# IEPE_POWER.net
KiCad netlist of a schematic drawn in Altium Designer
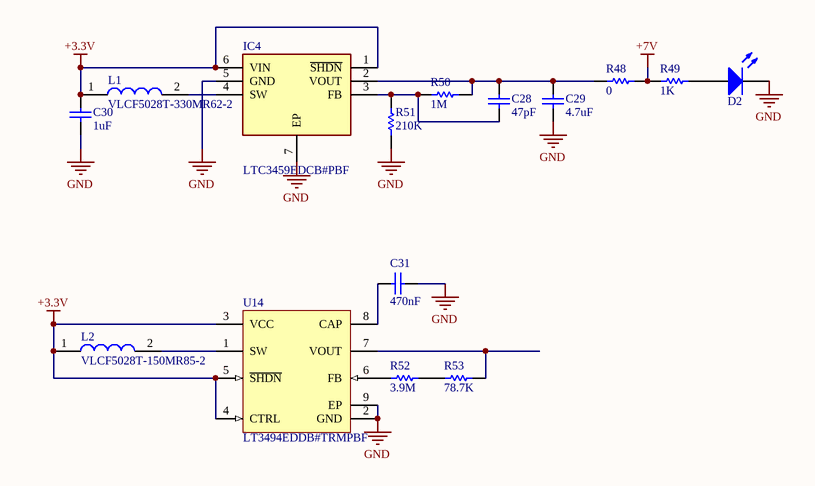
[diagram p0: IEPE_POWER.SchDoc]

(export (version "E")
  (design (tool "Eeschema 10.0.6"))
  (components
    (comp (ref "C28")
      (value "47pF")
      (footprint "c603")
      (description "Capacitor")
      (fields (field (name "DESIGNER") "Parsa Malekpour"))
      (libsource (lib "ParsaLibrary") (part "Cap"))
    )
    (comp (ref "C29")
      (value "4.7uF")
      (footprint "C805")
      (description "Capacitor")
      (fields (field (name "DESIGNER") "Parsa Malekpour"))
      (libsource (lib "ParsaLibrary") (part "Cap"))
    )
    (comp (ref "C30")
      (value "1uF")
      (footprint "c603")
      (description "Capacitor")
      (fields (field (name "DESIGNER") "Parsa Malekpour"))
      (libsource (lib "ParsaLibrary") (part "Cap"))
    )
    (comp (ref "C31")
      (value "470nF")
      (footprint "c603")
      (description "Capacitor")
      (fields (field (name "DESIGNER") "Parsa Malekpour"))
      (libsource (lib "ParsaLibrary") (part "Cap"))
    )
    (comp (ref "D2") (value "LED") (footprint "led-0603") (libsource (lib "ParsaLibrary") (part "LED")))
    (comp (ref "IC4")
      (value "LTC3459EDCB#PBF")
      (footprint "SamacSys:SON50P300X200X80-7N-D")
      (description "Integrated Circuit")
      (fields (field (name "MOUSER PART NUMBER") "584-LTC3459EDCB#PBF"))
      (libsource (lib "*") (part "LTC3459EDCB#PBF"))
    )
    (comp (ref "L1")
      (value "VLCF5028T-330MR62-2")
      (footprint "SamacSys:VLCF5028")
      (description "Inductor")
      (fields (field (name "MOUSER PART NUMBER") "810-VLCF528T330MR622"))
      (libsource (lib "*") (part "VLCF5028T-330MR62-2"))
    )
    (comp (ref "L2")
      (value "VLCF5028T-150MR85-2")
      (footprint "SamacSys:VLCF5028")
      (description "Inductor")
      (fields (field (name "MOUSER PART NUMBER") "810-VLCF528T150MR852"))
      (libsource (lib "*") (part "VLCF5028T-150MR85-2"))
    )
    (comp (ref "R48")
      (value "0")
      (footprint "R0603")
      (description "Resistor")
      (fields (field (name "DESIGNER") "Parsa Malekpour"))
      (libsource (lib "ParsaLibrary") (part "Resistor"))
    )
    (comp (ref "R49")
      (value "1K")
      (footprint "R0603")
      (description "Resistor")
      (fields (field (name "DESIGNER") "Parsa Malekpour"))
      (libsource (lib "ParsaLibrary") (part "Resistor"))
    )
    (comp (ref "R50")
      (value "1M")
      (footprint "R0603")
      (description "Resistor")
      (fields (field (name "DESIGNER") "Parsa Malekpour"))
      (libsource (lib "ParsaLibrary") (part "Resistor"))
    )
    (comp (ref "R51")
      (value "210K")
      (footprint "R0603")
      (description "Resistor")
      (fields (field (name "DESIGNER") "Parsa Malekpour"))
      (libsource (lib "ParsaLibrary") (part "Resistor"))
    )
    (comp (ref "R52")
      (value "3.9M")
      (footprint "R0603")
      (description "Resistor")
      (fields (field (name "DESIGNER") "Parsa Malekpour"))
      (libsource (lib "ParsaLibrary") (part "Resistor"))
    )
    (comp (ref "R53")
      (value "78.7K")
      (footprint "R0603")
      (description "Resistor")
      (fields (field (name "DESIGNER") "Parsa Malekpour"))
      (libsource (lib "ParsaLibrary") (part "Resistor"))
    )
    (comp (ref "U14")
      (value "LT3494EDDB#TRMPBF")
      (footprint "LT-DDB-8_V")
      (fields (field (name "MANUFACTURER") "Linear Technology"))
      (libsource (lib "Altium Content Vault") (part "LT-LT3494X-DDB-8_A"))
    )
  )
  (nets
    (net (code "1") (name "+3.3V") (class "Default")
      (node (ref "C30") (pin "2") (pinfunction "2_2") (pintype "passive"))
      (node (ref "IC4") (pin "1") (pinfunction "~{SHDN}_1") (pintype "passive"))
      (node (ref "IC4") (pin "6") (pinfunction "VIN_6") (pintype "passive"))
      (node (ref "L1") (pin "1") (pinfunction "1_1") (pintype "passive"))
      (node (ref "L2") (pin "1") (pinfunction "1_1") (pintype "passive"))
      (node (ref "U14") (pin "3") (pinfunction "VCC_3") (pintype "power_in"))
      (node (ref "U14") (pin "4") (pinfunction "CTRL_4") (pintype "input"))
      (node (ref "U14") (pin "5") (pinfunction "~{SHDN}_5") (pintype "input"))
    )
    (net (code "2") (name "+7V") (class "Default")
      (node (ref "R48") (pin "2") (pinfunction "2_2") (pintype "passive"))
      (node (ref "R49") (pin "1") (pinfunction "1_1") (pintype "passive"))
    )
    (net (code "3") (name "GND") (class "Default")
      (node (ref "C29") (pin "1") (pinfunction "1_1") (pintype "passive"))
      (node (ref "C30") (pin "1") (pinfunction "1_1") (pintype "passive"))
      (node (ref "C31") (pin "1") (pinfunction "1_1") (pintype "passive"))
      (node (ref "D2") (pin "2") (pinfunction "K_2") (pintype "passive"))
      (node (ref "IC4") (pin "5") (pinfunction "GND_5") (pintype "passive"))
      (node (ref "IC4") (pin "7") (pinfunction "EP_7") (pintype "passive"))
      (node (ref "R51") (pin "1") (pinfunction "1_1") (pintype "passive"))
      (node (ref "U14") (pin "2") (pinfunction "GND_2") (pintype "power_in"))
      (node (ref "U14") (pin "9") (pinfunction "EP_9") (pintype "power_in"))
    )
    (net (code "4") (name "Net-(D2-A)") (class "Default")
      (node (ref "D2") (pin "1") (pinfunction "A_1") (pintype "passive"))
      (node (ref "R49") (pin "2") (pinfunction "2_2") (pintype "passive"))
    )
    (net (code "5") (name "Net-(IC4-FB)") (class "Default")
      (node (ref "C28") (pin "1") (pinfunction "1_1") (pintype "passive"))
      (node (ref "IC4") (pin "3") (pinfunction "FB_3") (pintype "passive"))
      (node (ref "R50") (pin "1") (pinfunction "1_1") (pintype "passive"))
      (node (ref "R51") (pin "2") (pinfunction "2_2") (pintype "passive"))
    )
    (net (code "6") (name "Net-(IC4-SW)") (class "Default")
      (node (ref "IC4") (pin "4") (pinfunction "SW_4") (pintype "passive"))
      (node (ref "L1") (pin "2") (pinfunction "2_2") (pintype "passive"))
    )
    (net (code "7") (name "Net-(IC4-VOUT)") (class "Default")
      (node (ref "C28") (pin "2") (pinfunction "2_2") (pintype "passive"))
      (node (ref "C29") (pin "2") (pinfunction "2_2") (pintype "passive"))
      (node (ref "IC4") (pin "2") (pinfunction "VOUT_2") (pintype "passive"))
      (node (ref "R48") (pin "1") (pinfunction "1_1") (pintype "passive"))
      (node (ref "R50") (pin "2") (pinfunction "2_2") (pintype "passive"))
    )
    (net (code "8") (name "Net-(R52-Pad2)") (class "Default")
      (node (ref "R52") (pin "2") (pinfunction "2_2") (pintype "passive"))
      (node (ref "R53") (pin "1") (pinfunction "1_1") (pintype "passive"))
    )
    (net (code "9") (name "Net-(U14-CAP)") (class "Default")
      (node (ref "C31") (pin "2") (pinfunction "2_2") (pintype "passive"))
      (node (ref "U14") (pin "8") (pinfunction "CAP_8") (pintype "passive"))
    )
    (net (code "10") (name "Net-(U14-FB)") (class "Default")
      (node (ref "R52") (pin "1") (pinfunction "1_1") (pintype "passive"))
      (node (ref "U14") (pin "6") (pinfunction "FB_6") (pintype "input"))
    )
    (net (code "11") (name "Net-(U14-SW)") (class "Default")
      (node (ref "L2") (pin "2") (pinfunction "2_2") (pintype "passive"))
      (node (ref "U14") (pin "1") (pinfunction "SW_1") (pintype "passive"))
    )
    (net (code "12") (name "Net-(U14-VOUT)") (class "Default")
      (node (ref "R53") (pin "2") (pinfunction "2_2") (pintype "passive"))
      (node (ref "U14") (pin "7") (pinfunction "VOUT_7") (pintype "power_in"))
    )
  )
)
